# SG1000_-_SMS_OD.net
KiCad netlist of a schematic drawn in EAGLE
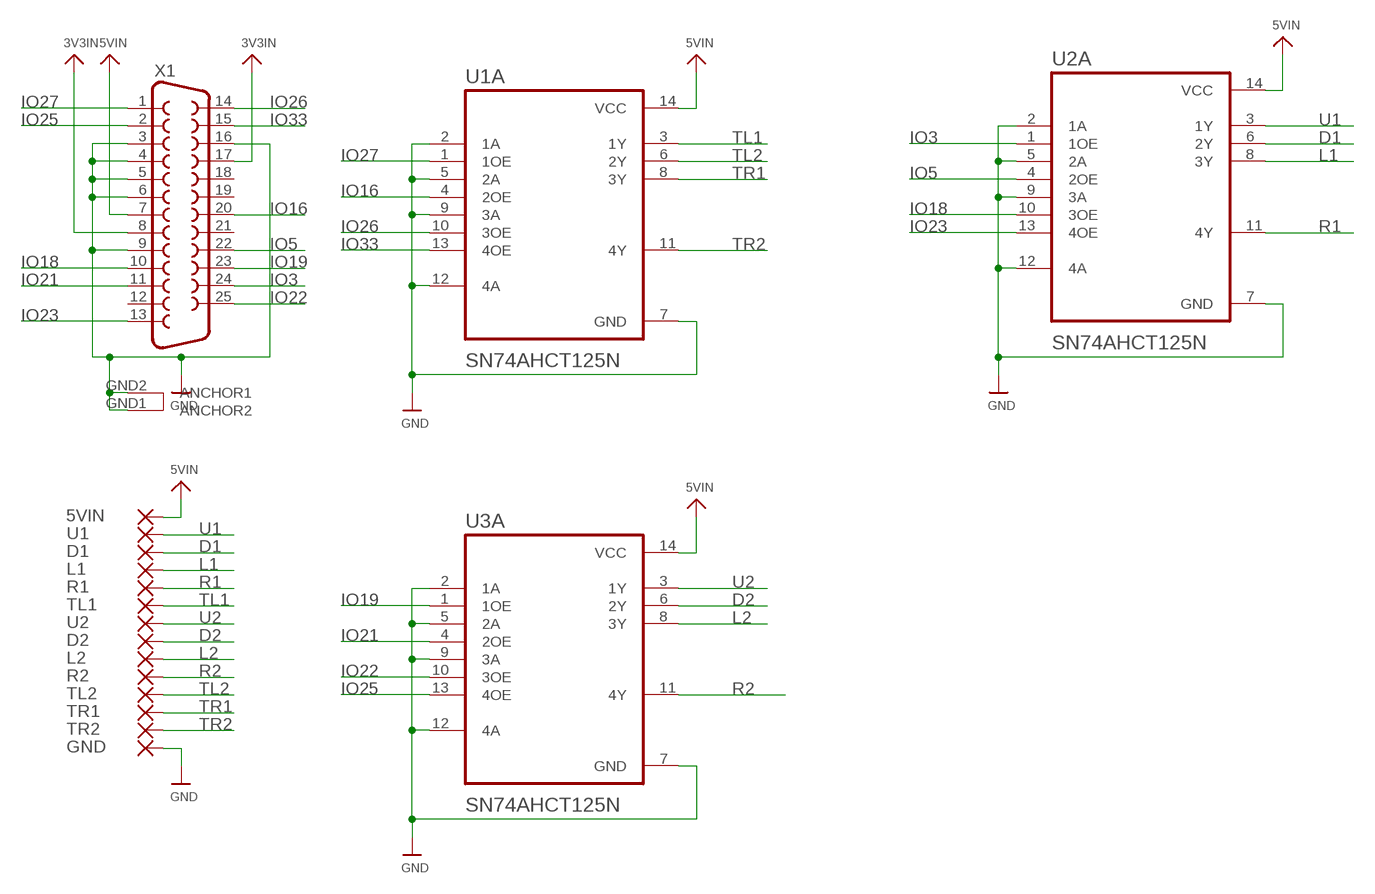
[diagram p0: schematic, sheet 1]

(export (version "E")
  (design (tool "Eeschema 10.0.6"))
  (components
    (comp (ref "5VIN")
      (value "SMD5")
      (footprint "eagle-import:SMD2,54-5,08")
      (libsource (lib "eagle-import") (part "SMD5"))
    )
    (comp (ref "D1")
      (value "SMD5")
      (footprint "eagle-import:SMD2,54-5,08")
      (libsource (lib "eagle-import") (part "SMD5"))
    )
    (comp (ref "D2")
      (value "SMD5")
      (footprint "eagle-import:SMD2,54-5,08")
      (libsource (lib "eagle-import") (part "SMD5"))
    )
    (comp (ref "GND")
      (value "SMD5")
      (footprint "eagle-import:SMD2,54-5,08")
      (libsource (lib "eagle-import") (part "SMD5"))
    )
    (comp (ref "L1")
      (value "SMD5")
      (footprint "eagle-import:SMD2,54-5,08")
      (libsource (lib "eagle-import") (part "SMD5"))
    )
    (comp (ref "L2")
      (value "SMD5")
      (footprint "eagle-import:SMD2,54-5,08")
      (libsource (lib "eagle-import") (part "SMD5"))
    )
    (comp (ref "R1")
      (value "SMD5")
      (footprint "eagle-import:SMD2,54-5,08")
      (libsource (lib "eagle-import") (part "SMD5"))
    )
    (comp (ref "R2")
      (value "SMD5")
      (footprint "eagle-import:SMD2,54-5,08")
      (libsource (lib "eagle-import") (part "SMD5"))
    )
    (comp (ref "TL1")
      (value "SMD5")
      (footprint "eagle-import:SMD2,54-5,08")
      (libsource (lib "eagle-import") (part "SMD5"))
    )
    (comp (ref "TL2")
      (value "SMD5")
      (footprint "eagle-import:SMD2,54-5,08")
      (libsource (lib "eagle-import") (part "SMD5"))
    )
    (comp (ref "TR1")
      (value "SMD5")
      (footprint "eagle-import:SMD2,54-5,08")
      (libsource (lib "eagle-import") (part "SMD5"))
    )
    (comp (ref "TR2")
      (value "SMD5")
      (footprint "eagle-import:SMD2,54-5,08")
      (libsource (lib "eagle-import") (part "SMD5"))
    )
    (comp (ref "U1")
      (value "SMD5")
      (footprint "eagle-import:SMD2,54-5,08")
      (libsource (lib "eagle-import") (part "SMD5"))
    )
    (comp (ref "U1A")
      (value "SN74AHCT125N")
      (footprint "eagle-import:DIP794W45P254L1969H508Q14")
      (fields (field (name "MF") "Texas Instruments"))
      (libsource (lib "eagle-import") (part "SN74AHCT125N"))
    )
    (comp (ref "U2")
      (value "SMD5")
      (footprint "eagle-import:SMD2,54-5,08")
      (libsource (lib "eagle-import") (part "SMD5"))
    )
    (comp (ref "U2A")
      (value "SN74AHCT125N")
      (footprint "eagle-import:DIP794W45P254L1969H508Q14")
      (fields (field (name "MF") "Texas Instruments"))
      (libsource (lib "eagle-import") (part "SN74AHCT125N"))
    )
    (comp (ref "U3A")
      (value "SN74AHCT125N")
      (footprint "eagle-import:DIP794W45P254L1969H508Q14")
      (fields (field (name "MF") "Texas Instruments"))
      (libsource (lib "eagle-import") (part "SN74AHCT125N"))
    )
    (comp (ref "X1")
      (value "DB25_FEMALEHP")
      (footprint "eagle-import:F25HP")
      (libsource (lib "eagle-import") (part "DB25_FEMALEHP"))
    )
  )
  (nets
    (net (code "1") (name "/D1") (class "Default")
      (node (ref "D1") (pin "1") (pinfunction "P_1") (pintype "passive"))
      (node (ref "U2A") (pin "6") (pinfunction "2Y_6") (pintype "output"))
    )
    (net (code "2") (name "/D2") (class "Default")
      (node (ref "D2") (pin "1") (pinfunction "P_1") (pintype "passive"))
      (node (ref "U3A") (pin "6") (pinfunction "2Y_6") (pintype "output"))
    )
    (net (code "3") (name "/IO3") (class "Default")
      (node (ref "U2A") (pin "1") (pinfunction "1OE_1") (pintype "input"))
      (node (ref "X1") (pin "24") (pinfunction "24_24") (pintype "passive"))
    )
    (net (code "4") (name "/IO5") (class "Default")
      (node (ref "U2A") (pin "4") (pinfunction "2OE_4") (pintype "input"))
      (node (ref "X1") (pin "22") (pinfunction "22_22") (pintype "passive"))
    )
    (net (code "5") (name "/IO16") (class "Default")
      (node (ref "U1A") (pin "4") (pinfunction "2OE_4") (pintype "input"))
      (node (ref "X1") (pin "20") (pinfunction "20_20") (pintype "passive"))
    )
    (net (code "6") (name "/IO18") (class "Default")
      (node (ref "U2A") (pin "10") (pinfunction "3OE_10") (pintype "input"))
      (node (ref "X1") (pin "10") (pinfunction "10_10") (pintype "passive"))
    )
    (net (code "7") (name "/IO19") (class "Default")
      (node (ref "U3A") (pin "1") (pinfunction "1OE_1") (pintype "input"))
      (node (ref "X1") (pin "23") (pinfunction "23_23") (pintype "passive"))
    )
    (net (code "8") (name "/IO21") (class "Default")
      (node (ref "U3A") (pin "4") (pinfunction "2OE_4") (pintype "input"))
      (node (ref "X1") (pin "11") (pinfunction "11_11") (pintype "passive"))
    )
    (net (code "9") (name "/IO22") (class "Default")
      (node (ref "U3A") (pin "10") (pinfunction "3OE_10") (pintype "input"))
      (node (ref "X1") (pin "25") (pinfunction "25_25") (pintype "passive"))
    )
    (net (code "10") (name "/IO23") (class "Default")
      (node (ref "U2A") (pin "13") (pinfunction "4OE_13") (pintype "input"))
      (node (ref "X1") (pin "13") (pinfunction "13_13") (pintype "passive"))
    )
    (net (code "11") (name "/IO25") (class "Default")
      (node (ref "U3A") (pin "13") (pinfunction "4OE_13") (pintype "input"))
      (node (ref "X1") (pin "2") (pinfunction "2_2") (pintype "passive"))
    )
    (net (code "12") (name "/IO26") (class "Default")
      (node (ref "U1A") (pin "10") (pinfunction "3OE_10") (pintype "input"))
      (node (ref "X1") (pin "14") (pinfunction "14_14") (pintype "passive"))
    )
    (net (code "13") (name "/IO27") (class "Default")
      (node (ref "U1A") (pin "1") (pinfunction "1OE_1") (pintype "input"))
      (node (ref "X1") (pin "1") (pinfunction "1_1") (pintype "passive"))
    )
    (net (code "14") (name "/IO33") (class "Default")
      (node (ref "U1A") (pin "13") (pinfunction "4OE_13") (pintype "input"))
      (node (ref "X1") (pin "15") (pinfunction "15_15") (pintype "passive"))
    )
    (net (code "15") (name "/L1") (class "Default")
      (node (ref "L1") (pin "1") (pinfunction "P_1") (pintype "passive"))
      (node (ref "U2A") (pin "8") (pinfunction "3Y_8") (pintype "output"))
    )
    (net (code "16") (name "/L2") (class "Default")
      (node (ref "L2") (pin "1") (pinfunction "P_1") (pintype "passive"))
      (node (ref "U3A") (pin "8") (pinfunction "3Y_8") (pintype "output"))
    )
    (net (code "17") (name "/R1") (class "Default")
      (node (ref "R1") (pin "1") (pinfunction "P_1") (pintype "passive"))
      (node (ref "U2A") (pin "11") (pinfunction "4Y_11") (pintype "output"))
    )
    (net (code "18") (name "/R2") (class "Default")
      (node (ref "R2") (pin "1") (pinfunction "P_1") (pintype "passive"))
      (node (ref "U3A") (pin "11") (pinfunction "4Y_11") (pintype "output"))
    )
    (net (code "19") (name "/TL1") (class "Default")
      (node (ref "TL1") (pin "1") (pinfunction "P_1") (pintype "passive"))
      (node (ref "U1A") (pin "3") (pinfunction "1Y_3") (pintype "output"))
    )
    (net (code "20") (name "/TL2") (class "Default")
      (node (ref "TL2") (pin "1") (pinfunction "P_1") (pintype "passive"))
      (node (ref "U1A") (pin "6") (pinfunction "2Y_6") (pintype "output"))
    )
    (net (code "21") (name "/TR1") (class "Default")
      (node (ref "TR1") (pin "1") (pinfunction "P_1") (pintype "passive"))
      (node (ref "U1A") (pin "8") (pinfunction "3Y_8") (pintype "output"))
    )
    (net (code "22") (name "/TR2") (class "Default")
      (node (ref "TR2") (pin "1") (pinfunction "P_1") (pintype "passive"))
      (node (ref "U1A") (pin "11") (pinfunction "4Y_11") (pintype "output"))
    )
    (net (code "23") (name "/U1") (class "Default")
      (node (ref "U1") (pin "1") (pinfunction "P_1") (pintype "passive"))
      (node (ref "U2A") (pin "3") (pinfunction "1Y_3") (pintype "output"))
    )
    (net (code "24") (name "/U2") (class "Default")
      (node (ref "U2") (pin "1") (pinfunction "P_1") (pintype "passive"))
      (node (ref "U3A") (pin "3") (pinfunction "1Y_3") (pintype "output"))
    )
    (net (code "25") (name "3V3IN") (class "Default")
      (node (ref "X1") (pin "17") (pinfunction "17_17") (pintype "passive"))
      (node (ref "X1") (pin "8") (pinfunction "8_8") (pintype "passive"))
    )
    (net (code "26") (name "5VIN") (class "Default")
      (node (ref "5VIN") (pin "1") (pinfunction "P_1") (pintype "passive"))
      (node (ref "U1A") (pin "14") (pinfunction "VCC_14") (pintype "power_in"))
      (node (ref "U2A") (pin "14") (pinfunction "VCC_14") (pintype "power_in"))
      (node (ref "U3A") (pin "14") (pinfunction "VCC_14") (pintype "power_in"))
      (node (ref "X1") (pin "7") (pinfunction "7_7") (pintype "passive"))
    )
    (net (code "27") (name "GND") (class "Default")
      (node (ref "GND") (pin "1") (pinfunction "P_1") (pintype "passive"))
      (node (ref "U1A") (pin "12") (pinfunction "4A_12") (pintype "bidirectional"))
      (node (ref "U1A") (pin "2") (pinfunction "1A_2") (pintype "input"))
      (node (ref "U1A") (pin "5") (pinfunction "2A_5") (pintype "input"))
      (node (ref "U1A") (pin "7") (pinfunction "GND_7") (pintype "power_in"))
      (node (ref "U1A") (pin "9") (pinfunction "3A_9") (pintype "input"))
      (node (ref "U2A") (pin "12") (pinfunction "4A_12") (pintype "bidirectional"))
      (node (ref "U2A") (pin "2") (pinfunction "1A_2") (pintype "input"))
      (node (ref "U2A") (pin "5") (pinfunction "2A_5") (pintype "input"))
      (node (ref "U2A") (pin "7") (pinfunction "GND_7") (pintype "power_in"))
      (node (ref "U2A") (pin "9") (pinfunction "3A_9") (pintype "input"))
      (node (ref "U3A") (pin "12") (pinfunction "4A_12") (pintype "bidirectional"))
      (node (ref "U3A") (pin "2") (pinfunction "1A_2") (pintype "input"))
      (node (ref "U3A") (pin "5") (pinfunction "2A_5") (pintype "input"))
      (node (ref "U3A") (pin "7") (pinfunction "GND_7") (pintype "power_in"))
      (node (ref "U3A") (pin "9") (pinfunction "3A_9") (pintype "input"))
      (node (ref "X1") (pin "16") (pinfunction "16_16") (pintype "passive"))
      (node (ref "X1") (pin "3") (pinfunction "3_3") (pintype "passive"))
      (node (ref "X1") (pin "4") (pinfunction "4_4") (pintype "passive"))
      (node (ref "X1") (pin "5") (pinfunction "5_5") (pintype "passive"))
      (node (ref "X1") (pin "6") (pinfunction "6_6") (pintype "passive"))
      (node (ref "X1") (pin "9") (pinfunction "9_9") (pintype "passive"))
      (node (ref "X1") (pin "GND1") (pinfunction "ANCHOR2_GND1") (pintype "bidirectional"))
      (node (ref "X1") (pin "GND2") (pinfunction "ANCHOR1_GND2") (pintype "bidirectional"))
    )
    (net (code "28") (name "unconnected-(X1-Pad12)") (class "Default")
      (node (ref "X1") (pin "12") (pinfunction "12_12") (pintype "passive"))
    )
    (net (code "29") (name "unconnected-(X1-Pad18)") (class "Default")
      (node (ref "X1") (pin "18") (pinfunction "18_18") (pintype "passive"))
    )
    (net (code "30") (name "unconnected-(X1-Pad19)") (class "Default")
      (node (ref "X1") (pin "19") (pinfunction "19_19") (pintype "passive"))
    )
    (net (code "31") (name "unconnected-(X1-Pad21)") (class "Default")
      (node (ref "X1") (pin "21") (pinfunction "21_21") (pintype "passive"))
    )
  )
)
